# dcb_top.net
KiCad netlist of a schematic drawn in Altium Designer
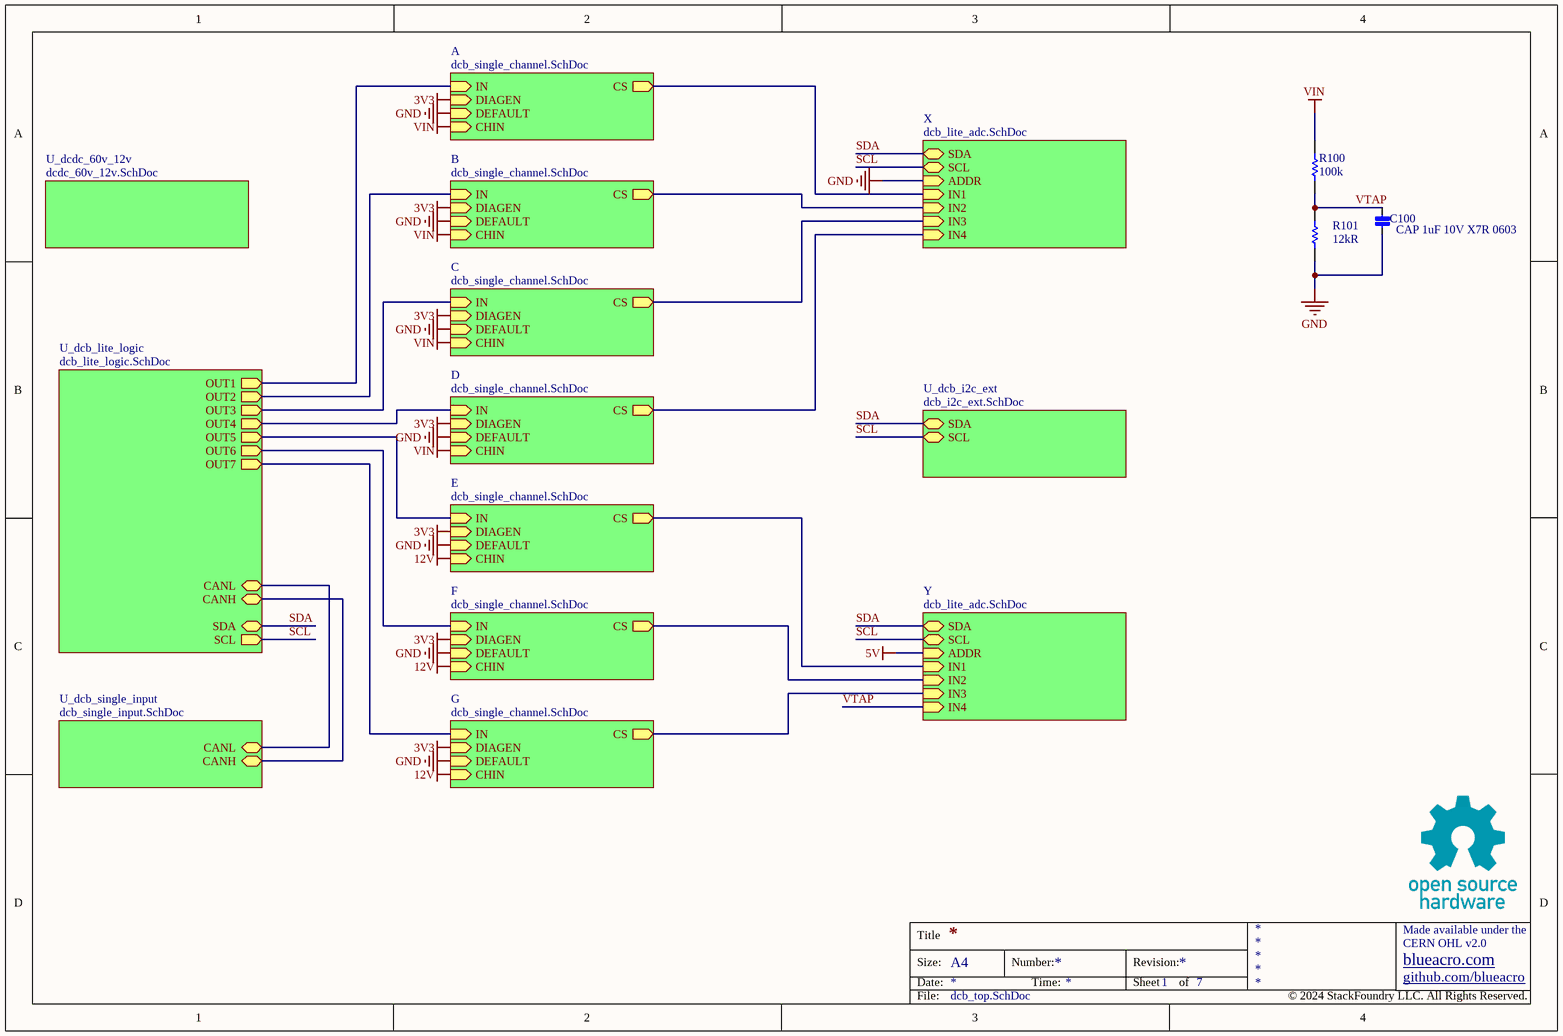
[diagram p0: dcb_top.SchDoc]

(export (version "E")
  (design (tool "Eeschema 10.0.6"))
  (components
    (comp (ref "C100")
      (value "CAP 1uF 10V X7R 0603")
      (footprint "FP-CL10-IPC_B")
      (description "Cap Ceramic 1uF 10V X7R 10% SMD 0603 125C Paper T/R")
      (libsource (lib "StackFoundry LLC") (part "C-EU"))
    )
    (comp (ref "R100")
      (value "100k")
      (footprint "RESC1608-IPC-LL")
      (description "SMD Chip Resistor, 100 kOhm, ± 1%, 100 mW, 0603 [1608 Metric], Thick Film, General Purpose")
      (fields (field (name "TOLERANCE") "1%") (field (name "Comment") "100k 0603 1%"))
      (libsource (lib "StackFoundry LLC") (part "RES"))
    )
    (comp (ref "R101")
      (value "12kR")
      (footprint "RESC1608X55X25LL10T15")
      (description "SMD Chip Resistor, 12 kOhm, ± 1%, 100 mW, 0603 [1608 Metric], Thick Film, General Purpose")
      (fields (field (name "TOLERANCE") "1%") (field (name "Comment") "12k 0603 1%"))
      (libsource (lib "StackFoundry LLC") (part "RES-2"))
    )
  )
  (nets
    (net (code "19") (name "/VTAP") (class "Default")
      (node (ref "C100") (pin "1") (pinfunction "1_1") (pintype "passive"))
      (node (ref "R100") (pin "1") (pinfunction "1_1") (pintype "passive"))
      (node (ref "R101") (pin "2") (pinfunction "2_2") (pintype "passive"))
    )
    (net (code "23") (name "GND") (class "Default")
      (node (ref "C100") (pin "2") (pinfunction "2_2") (pintype "passive"))
      (node (ref "R101") (pin "1") (pinfunction "1_1") (pintype "passive"))
    )
    (net (code "24") (name "VIN") (class "Default")
      (node (ref "R100") (pin "2") (pinfunction "2_2") (pintype "passive"))
    )
  )
)
